# BOTTOM_BOARD_TRANS.net
KiCad netlist of a schematic drawn in Altium Designer
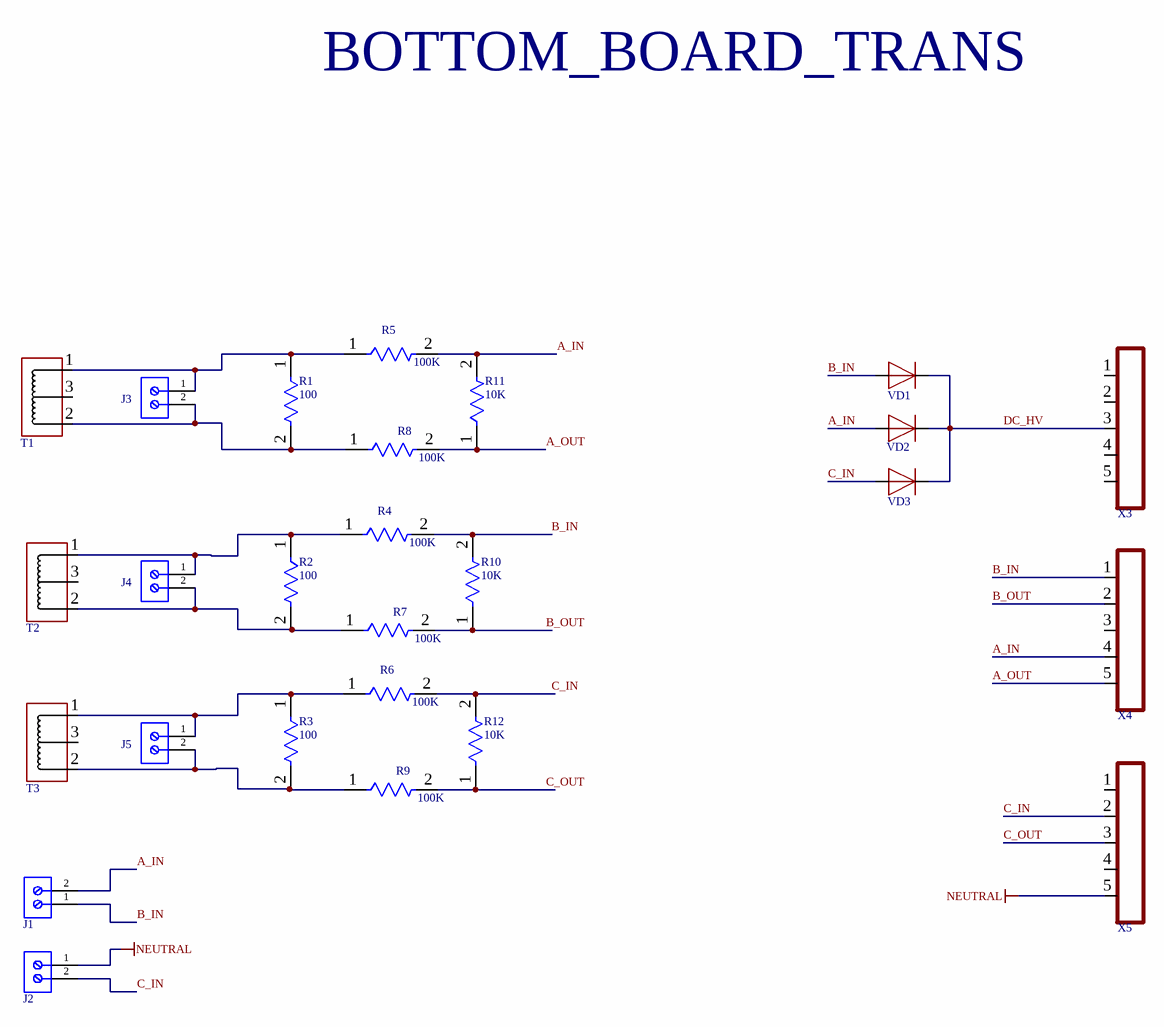
[diagram p0: BOTTOM_BOARD_TRANS.SchDoc]

(export (version "E")
  (design (tool "Eeschema 10.0.6"))
  (components
    (comp (ref "J1")
      (value "691213510002")
      (footprint "691213510002")
      (description "WR-TBL Series 2135 Horizontal Entry Modular, THT, pitch 5.08mm, 2p")
      (fields (field (name "MANUFACTURER") "Wurth Elektronik"))
      (libsource (lib "Altium_WR-TBL (rev23d)") (part "691213510002"))
    )
    (comp (ref "J2")
      (value "691213510002")
      (footprint "691213510002")
      (description "WR-TBL Series 2135 Horizontal Entry Modular, THT, pitch 5.08mm, 2p")
      (fields (field (name "MANUFACTURER") "Wurth Elektronik"))
      (libsource (lib "Altium_WR-TBL (rev23d)") (part "691213510002"))
    )
    (comp (ref "J3")
      (value "691213510002")
      (footprint "691213510002")
      (description "WR-TBL Series 2135 Horizontal Entry Modular, THT, pitch 5.08mm, 2p")
      (fields (field (name "MANUFACTURER") "Wurth Elektronik"))
      (libsource (lib "Altium_WR-TBL (rev23d)") (part "691213510002"))
    )
    (comp (ref "J4")
      (value "691213510002")
      (footprint "691213510002")
      (description "WR-TBL Series 2135 Horizontal Entry Modular, THT, pitch 5.08mm, 2p")
      (fields (field (name "MANUFACTURER") "Wurth Elektronik"))
      (libsource (lib "Altium_WR-TBL (rev23d)") (part "691213510002"))
    )
    (comp (ref "J5")
      (value "691213510002")
      (footprint "691213510002")
      (description "WR-TBL Series 2135 Horizontal Entry Modular, THT, pitch 5.08mm, 2p")
      (fields (field (name "MANUFACTURER") "Wurth Elektronik"))
      (libsource (lib "Altium_WR-TBL (rev23d)") (part "691213510002"))
    )
    (comp (ref "R1")
      (value "100")
      (footprint "RES-2512")
      (description "10K")
      (libsource (lib "PASSIVE_COMPONENTS") (part "RES-CONST"))
    )
    (comp (ref "R2")
      (value "100")
      (footprint "RES-2512")
      (description "10K")
      (libsource (lib "PASSIVE_COMPONENTS") (part "RES-CONST"))
    )
    (comp (ref "R3")
      (value "100")
      (footprint "RES-2512")
      (description "10K")
      (libsource (lib "PASSIVE_COMPONENTS") (part "RES-CONST"))
    )
    (comp (ref "R4")
      (value "100K")
      (footprint "RES-0805")
      (description "10K")
      (libsource (lib "PASSIVE_COMPONENTS") (part "RES-CONST"))
    )
    (comp (ref "R5")
      (value "100K")
      (footprint "RES-0805")
      (description "10K")
      (libsource (lib "PASSIVE_COMPONENTS") (part "RES-CONST"))
    )
    (comp (ref "R6")
      (value "100K")
      (footprint "RES-0805")
      (description "10K")
      (libsource (lib "PASSIVE_COMPONENTS") (part "RES-CONST"))
    )
    (comp (ref "R7")
      (value "100K")
      (footprint "RES-0805")
      (description "10K")
      (libsource (lib "PASSIVE_COMPONENTS") (part "RES-CONST"))
    )
    (comp (ref "R8")
      (value "100K")
      (footprint "RES-0805")
      (description "10K")
      (libsource (lib "PASSIVE_COMPONENTS") (part "RES-CONST"))
    )
    (comp (ref "R9")
      (value "100K")
      (footprint "RES-0805")
      (description "10K")
      (libsource (lib "PASSIVE_COMPONENTS") (part "RES-CONST"))
    )
    (comp (ref "R10")
      (value "10K")
      (footprint "RES-0805")
      (libsource (lib "PASSIVE_COMPONENTS") (part "RES-CONST"))
    )
    (comp (ref "R11")
      (value "10K")
      (footprint "RES-0805")
      (libsource (lib "PASSIVE_COMPONENTS") (part "RES-CONST"))
    )
    (comp (ref "R12")
      (value "10K")
      (footprint "RES-0805")
      (libsource (lib "PASSIVE_COMPONENTS") (part "RES-CONST"))
    )
    (comp (ref "T1") (value "AC1005") (footprint "AC1005") (libsource (lib "AC1005") (part "AC1005")))
    (comp (ref "T2") (value "AC1005") (footprint "AC1005") (libsource (lib "AC1005") (part "AC1005")))
    (comp (ref "T3") (value "AC1005") (footprint "AC1005") (libsource (lib "AC1005") (part "AC1005")))
    (comp (ref "VD1")
      (value "DIODE")
      (footprint "DO-214BA")
      (libsource (lib "PASSIVE_COMPONENTS") (part "DIODE"))
    )
    (comp (ref "VD2")
      (value "DIODE")
      (footprint "DO-214BA")
      (libsource (lib "PASSIVE_COMPONENTS") (part "DIODE"))
    )
    (comp (ref "VD3")
      (value "DIODE")
      (footprint "DO-214BA")
      (libsource (lib "PASSIVE_COMPONENTS") (part "DIODE"))
    )
    (comp (ref "X3")
      (value "CONN-5-PIN")
      (footprint "CONN-PLS-5-2.54mm")
      (libsource (lib "PLS-5_M") (part "CONN-5-PIN"))
    )
    (comp (ref "X4")
      (value "CONN-5-PIN")
      (footprint "CONN-PLS-5-2.54mm")
      (libsource (lib "PLS-5_M") (part "CONN-5-PIN"))
    )
    (comp (ref "X5")
      (value "CONN-5-PIN")
      (footprint "CONN-PLS-5-2.54mm")
      (libsource (lib "PLS-5_M") (part "CONN-5-PIN"))
    )
  )
  (nets
    (net (code "1") (name "/A_IN") (class "Default")
      (node (ref "J1") (pin "2") (pinfunction "2_2") (pintype "passive"))
      (node (ref "R11") (pin "2") (pinfunction "2_2") (pintype "passive"))
      (node (ref "R5") (pin "2") (pinfunction "2_2") (pintype "passive"))
      (node (ref "VD2") (pin "2") (pinfunction "A_2") (pintype "passive"))
      (node (ref "X4") (pin "4") (pinfunction "4_4") (pintype "passive"))
    )
    (net (code "2") (name "/A_OUT") (class "Default")
      (node (ref "R11") (pin "1") (pinfunction "1_1") (pintype "passive"))
      (node (ref "R8") (pin "2") (pinfunction "2_2") (pintype "passive"))
      (node (ref "X4") (pin "5") (pinfunction "5_5") (pintype "passive"))
    )
    (net (code "3") (name "/B_IN") (class "Default")
      (node (ref "J1") (pin "1") (pinfunction "1_1") (pintype "passive"))
      (node (ref "R10") (pin "2") (pinfunction "2_2") (pintype "passive"))
      (node (ref "R4") (pin "2") (pinfunction "2_2") (pintype "passive"))
      (node (ref "VD1") (pin "2") (pinfunction "A_2") (pintype "passive"))
      (node (ref "X4") (pin "1") (pinfunction "1_1") (pintype "passive"))
    )
    (net (code "4") (name "/B_OUT") (class "Default")
      (node (ref "R10") (pin "1") (pinfunction "1_1") (pintype "passive"))
      (node (ref "R7") (pin "2") (pinfunction "2_2") (pintype "passive"))
      (node (ref "X4") (pin "2") (pinfunction "2_2") (pintype "passive"))
    )
    (net (code "5") (name "/C_IN") (class "Default")
      (node (ref "J2") (pin "2") (pinfunction "2_2") (pintype "passive"))
      (node (ref "R12") (pin "2") (pinfunction "2_2") (pintype "passive"))
      (node (ref "R6") (pin "2") (pinfunction "2_2") (pintype "passive"))
      (node (ref "VD3") (pin "2") (pinfunction "A_2") (pintype "passive"))
      (node (ref "X5") (pin "2") (pinfunction "2_2") (pintype "passive"))
    )
    (net (code "6") (name "/C_OUT") (class "Default")
      (node (ref "R12") (pin "1") (pinfunction "1_1") (pintype "passive"))
      (node (ref "R9") (pin "2") (pinfunction "2_2") (pintype "passive"))
      (node (ref "X5") (pin "3") (pinfunction "3_3") (pintype "passive"))
    )
    (net (code "7") (name "/DC_HV") (class "Default")
      (node (ref "VD1") (pin "1") (pinfunction "C_1") (pintype "passive"))
      (node (ref "VD2") (pin "1") (pinfunction "C_1") (pintype "passive"))
      (node (ref "VD3") (pin "1") (pinfunction "C_1") (pintype "passive"))
      (node (ref "X3") (pin "3") (pinfunction "3_3") (pintype "passive"))
    )
    (net (code "8") (name "NEUTRAL") (class "Default")
      (node (ref "J2") (pin "1") (pinfunction "1_1") (pintype "passive"))
      (node (ref "X5") (pin "5") (pinfunction "5_5") (pintype "passive"))
    )
    (net (code "9") (name "Net-(J3-Pad2)") (class "Default")
      (node (ref "J3") (pin "2") (pinfunction "2_2") (pintype "passive"))
      (node (ref "R1") (pin "2") (pinfunction "2_2") (pintype "passive"))
      (node (ref "R8") (pin "1") (pinfunction "1_1") (pintype "passive"))
      (node (ref "T1") (pin "2") (pinfunction "2_2") (pintype "passive"))
    )
    (net (code "10") (name "Net-(J4-Pad2)") (class "Default")
      (node (ref "J4") (pin "2") (pinfunction "2_2") (pintype "passive"))
      (node (ref "R2") (pin "2") (pinfunction "2_2") (pintype "passive"))
      (node (ref "R7") (pin "1") (pinfunction "1_1") (pintype "passive"))
      (node (ref "T2") (pin "2") (pinfunction "2_2") (pintype "passive"))
    )
    (net (code "11") (name "Net-(J5-Pad2)") (class "Default")
      (node (ref "J5") (pin "2") (pinfunction "2_2") (pintype "passive"))
      (node (ref "R3") (pin "2") (pinfunction "2_2") (pintype "passive"))
      (node (ref "R9") (pin "1") (pinfunction "1_1") (pintype "passive"))
      (node (ref "T3") (pin "2") (pinfunction "2_2") (pintype "passive"))
    )
    (net (code "12") (name "Net-(T1-17)") (class "Default")
      (node (ref "J3") (pin "1") (pinfunction "1_1") (pintype "passive"))
      (node (ref "R1") (pin "1") (pinfunction "1_1") (pintype "passive"))
      (node (ref "R5") (pin "1") (pinfunction "1_1") (pintype "passive"))
      (node (ref "T1") (pin "1") (pinfunction "17_1") (pintype "passive"))
    )
    (net (code "13") (name "Net-(T2-17)") (class "Default")
      (node (ref "J4") (pin "1") (pinfunction "1_1") (pintype "passive"))
      (node (ref "R2") (pin "1") (pinfunction "1_1") (pintype "passive"))
      (node (ref "R4") (pin "1") (pinfunction "1_1") (pintype "passive"))
      (node (ref "T2") (pin "1") (pinfunction "17_1") (pintype "passive"))
    )
    (net (code "14") (name "Net-(T3-17)") (class "Default")
      (node (ref "J5") (pin "1") (pinfunction "1_1") (pintype "passive"))
      (node (ref "R3") (pin "1") (pinfunction "1_1") (pintype "passive"))
      (node (ref "R6") (pin "1") (pinfunction "1_1") (pintype "passive"))
      (node (ref "T3") (pin "1") (pinfunction "17_1") (pintype "passive"))
    )
    (net (code "15") (name "unconnected-(T1-Pad3)") (class "Default")
      (node (ref "T1") (pin "3") (pinfunction "3_3") (pintype "passive"))
    )
    (net (code "16") (name "unconnected-(T2-Pad3)") (class "Default")
      (node (ref "T2") (pin "3") (pinfunction "3_3") (pintype "passive"))
    )
    (net (code "17") (name "unconnected-(T3-Pad3)") (class "Default")
      (node (ref "T3") (pin "3") (pinfunction "3_3") (pintype "passive"))
    )
    (net (code "18") (name "unconnected-(X3-Pad1)") (class "Default")
      (node (ref "X3") (pin "1") (pinfunction "1_1") (pintype "passive"))
    )
    (net (code "19") (name "unconnected-(X3-Pad2)") (class "Default")
      (node (ref "X3") (pin "2") (pinfunction "2_2") (pintype "passive"))
    )
    (net (code "20") (name "unconnected-(X3-Pad4)") (class "Default")
      (node (ref "X3") (pin "4") (pinfunction "4_4") (pintype "passive"))
    )
    (net (code "21") (name "unconnected-(X3-Pad5)") (class "Default")
      (node (ref "X3") (pin "5") (pinfunction "5_5") (pintype "passive"))
    )
    (net (code "22") (name "unconnected-(X4-Pad3)") (class "Default")
      (node (ref "X4") (pin "3") (pinfunction "3_3") (pintype "passive"))
    )
    (net (code "23") (name "unconnected-(X5-Pad1)") (class "Default")
      (node (ref "X5") (pin "1") (pinfunction "1_1") (pintype "passive"))
    )
    (net (code "24") (name "unconnected-(X5-Pad4)") (class "Default")
      (node (ref "X5") (pin "4") (pinfunction "4_4") (pintype "passive"))
    )
  )
)
